# LabAccessDC.net
KiCad netlist of a schematic drawn in EAGLE
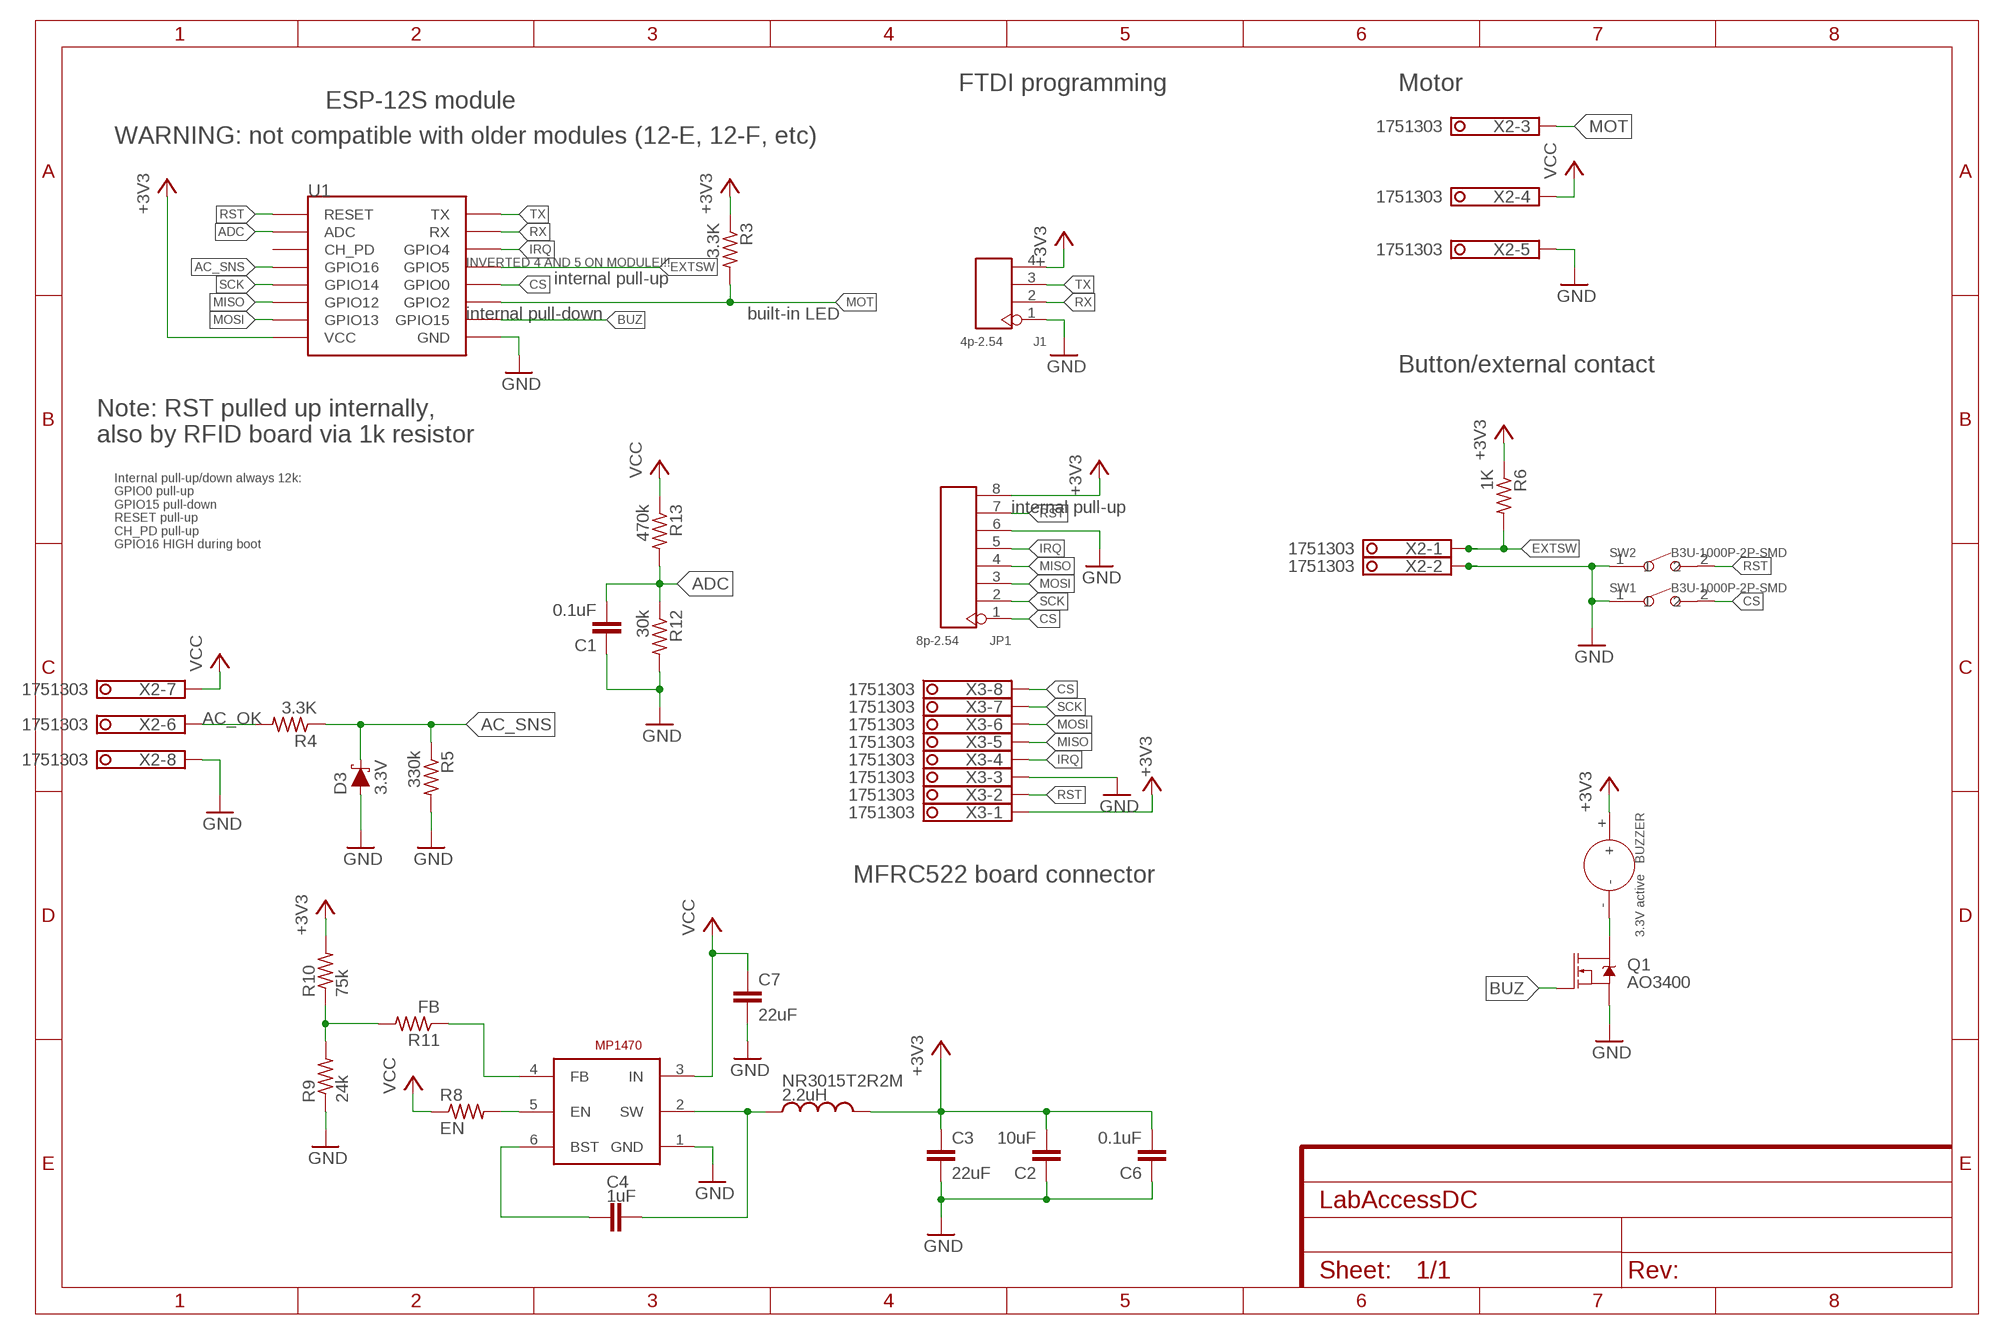
[diagram p0: schematic, sheet 1]

(export (version "E")
  (design (tool "Eeschema 10.0.6"))
  (components
    (comp (ref "BUZZER")
      (value "3.3V active")
      (footprint "eagle-import:BZ2-7.6-D12.0XH6.5MM")
      (fields (field (name "MPN") "KS-12065D03YA"))
      (libsource (lib "eagle-import") (part "DIP-BUZZER-3V(KS-12065D03YA)"))
    )
    (comp (ref "C1")
      (value "0.1uF")
      (footprint "eagle-import:C0603K")
      (libsource (lib "eagle-import") (part "C-EUC0603K"))
    )
    (comp (ref "C2")
      (value "10uF")
      (footprint "eagle-import:C0805K")
      (libsource (lib "eagle-import") (part "C-EUC0805K"))
    )
    (comp (ref "C3")
      (value "22uF")
      (footprint "eagle-import:C0805K")
      (libsource (lib "eagle-import") (part "C-EUC0805K"))
    )
    (comp (ref "C4")
      (value "1uF")
      (footprint "eagle-import:C0603K")
      (libsource (lib "eagle-import") (part "C-EUC0603K"))
    )
    (comp (ref "C6")
      (value "0.1uF")
      (footprint "eagle-import:C0603K")
      (libsource (lib "eagle-import") (part "C-EUC0603K"))
    )
    (comp (ref "C7")
      (value "22uF")
      (footprint "eagle-import:C0805K")
      (libsource (lib "eagle-import") (part "C-EUC0805K"))
    )
    (comp (ref "D3")
      (value "3.3V")
      (footprint "eagle-import:SPARKFUN-DISCRETESEMI_SOD-523")
      (fields (field (name "SPICEPREFIX") "D"))
      (libsource (lib "eagle-import") (part "SPARKFUN-DISCRETESEMI_DIODE-SCHOTTKY-RB751S40"))
    )
    (comp (ref "J1")
      (value "4p-2.54")
      (footprint "eagle-import:H4-2.54")
      (fields (field (name "MPN") "P125-1104A0BS116A1"))
      (libsource (lib "eagle-import") (part "DIP-BLACK-MALE-HEADER-VERT(4P-2.54)"))
    )
    (comp (ref "JP1")
      (value "8p-2.54")
      (footprint "eagle-import:H8-2.54")
      (fields (field (name "MPN") "P125-1108A1BS116A1"))
      (libsource (lib "eagle-import") (part "DIP-BLACK-MALE-HEADER-VERT(8P-2.54)"))
    )
    (comp (ref "MP1470")
      (value "MP1470GJ")
      (footprint "eagle-import:TSOT-23-6")
      (libsource (lib "eagle-import") (part "MP1470GJ"))
    )
    (comp (ref "NR3015T2R2M")
      (value "2.2uH")
      (footprint "eagle-import:INDUCTOR-NR3015")
      (libsource (lib "eagle-import") (part "INDUCTORB"))
    )
    (comp (ref "Q1")
      (value "AO3400")
      (footprint "eagle-import:SOT23-3")
      (libsource (lib "eagle-import") (part "MOSFET-NCH-AO3404A"))
    )
    (comp (ref "R3")
      (value "3.3K")
      (footprint "eagle-import:R0603")
      (libsource (lib "eagle-import") (part "resistor_348_R-US_R0603"))
    )
    (comp (ref "R4")
      (value "3.3K")
      (footprint "eagle-import:R0603")
      (libsource (lib "eagle-import") (part "R-US_R0603"))
    )
    (comp (ref "R5")
      (value "330k")
      (footprint "eagle-import:R0603")
      (libsource (lib "eagle-import") (part "R-US_R0603"))
    )
    (comp (ref "R6")
      (value "1K")
      (footprint "eagle-import:R0603")
      (libsource (lib "eagle-import") (part "resistor_348_R-US_R0603"))
    )
    (comp (ref "R8")
      (value "EN")
      (footprint "eagle-import:R0603")
      (libsource (lib "eagle-import") (part "R-US_R0603"))
    )
    (comp (ref "R9")
      (value "24k")
      (footprint "eagle-import:R0603")
      (libsource (lib "eagle-import") (part "R-US_R0603"))
    )
    (comp (ref "R10")
      (value "75k")
      (footprint "eagle-import:R0603")
      (libsource (lib "eagle-import") (part "R-US_R0603"))
    )
    (comp (ref "R11")
      (value "FB")
      (footprint "eagle-import:R0603")
      (libsource (lib "eagle-import") (part "R-US_R0603"))
    )
    (comp (ref "R12")
      (value "30k")
      (footprint "eagle-import:R0603")
      (libsource (lib "eagle-import") (part "R-US_R0603"))
    )
    (comp (ref "R13")
      (value "470k")
      (footprint "eagle-import:R0603")
      (libsource (lib "eagle-import") (part "R-US_R0603"))
    )
    (comp (ref "SW1")
      (value "B3U-1000P-2P-SMD")
      (footprint "eagle-import:SW2-2.6-3.0X2.5X1.2+0.4MM")
      (libsource (lib "eagle-import") (part "SMD-BUTTON(2P-3.0X2.5X1.2+0.4MM)-B3U-1000P-2P-SMD"))
    )
    (comp (ref "SW2")
      (value "B3U-1000P-2P-SMD")
      (footprint "eagle-import:SW2-2.6-3.0X2.5X1.2+0.4MM")
      (libsource (lib "eagle-import") (part "SMD-BUTTON(2P-3.0X2.5X1.2+0.4MM)-B3U-1000P-2P-SMD"))
    )
    (comp (ref "U1")
      (value "ESP12SMD")
      (footprint "eagle-import:ESP12-SMD")
      (libsource (lib "eagle-import") (part "ESP12SMD"))
    )
    (comp (ref "X2")
      (value "1751303")
      (footprint "eagle-import:1751303")
      (libsource (lib "eagle-import") (part "1751303"))
    )
    (comp (ref "X3")
      (value "1751303")
      (footprint "eagle-import:1751303")
      (libsource (lib "eagle-import") (part "1751303"))
    )
  )
  (nets
    (net (code "1") (name "+3V3") (class "Default")
      (node (ref "BUZZER") (pin "+") (pinfunction "+_+") (pintype "bidirectional"))
      (node (ref "C2") (pin "2") (pinfunction "2_2") (pintype "passive"))
      (node (ref "C3") (pin "1") (pinfunction "1_1") (pintype "passive"))
      (node (ref "C6") (pin "2") (pinfunction "2_2") (pintype "passive"))
      (node (ref "J1") (pin "4") (pinfunction "P$4_4") (pintype "bidirectional"))
      (node (ref "JP1") (pin "8") (pinfunction "8_8") (pintype "bidirectional"))
      (node (ref "NR3015T2R2M") (pin "2") (pinfunction "2_2") (pintype "passive"))
      (node (ref "R10") (pin "2") (pinfunction "2_2") (pintype "passive"))
      (node (ref "R3") (pin "1") (pinfunction "1_1") (pintype "passive"))
      (node (ref "R6") (pin "1") (pinfunction "1_1") (pintype "passive"))
      (node (ref "U1") (pin "VCC") (pinfunction "VCC_VCC") (pintype "bidirectional"))
      (node (ref "X3") (pin "1") (pinfunction "K_1") (pintype "passive"))
    )
    (net (code "2") (name "/AC_OK") (class "Default")
      (node (ref "R4") (pin "2") (pinfunction "2_2") (pintype "passive"))
      (node (ref "X2") (pin "6") (pinfunction "K_6") (pintype "passive"))
    )
    (net (code "3") (name "AC_SNS") (class "Default")
      (node (ref "D3") (pin "C") (pinfunction "C_C") (pintype "passive"))
      (node (ref "R4") (pin "1") (pinfunction "1_1") (pintype "passive"))
      (node (ref "R5") (pin "1") (pinfunction "1_1") (pintype "passive"))
      (node (ref "U1") (pin "GPIO16") (pinfunction "GPIO16_GPIO16") (pintype "bidirectional"))
    )
    (net (code "4") (name "ADC") (class "Default")
      (node (ref "C1") (pin "2") (pinfunction "2_2") (pintype "passive"))
      (node (ref "R12") (pin "1") (pinfunction "1_1") (pintype "passive"))
      (node (ref "R13") (pin "2") (pinfunction "2_2") (pintype "passive"))
      (node (ref "U1") (pin "ADC") (pinfunction "ADC_ADC") (pintype "bidirectional"))
    )
    (net (code "5") (name "BUZ") (class "Default")
      (node (ref "Q1") (pin "1") (pinfunction "G_1") (pintype "bidirectional"))
      (node (ref "U1") (pin "GPIO15") (pinfunction "GPIO15_GPIO15") (pintype "bidirectional"))
    )
    (net (code "6") (name "CS") (class "Default")
      (node (ref "JP1") (pin "1") (pinfunction "1_1") (pintype "bidirectional"))
      (node (ref "SW1") (pin "2") (pinfunction "2_2") (pintype "bidirectional"))
      (node (ref "U1") (pin "GPIO0") (pinfunction "GPIO0_GPIO0") (pintype "bidirectional"))
      (node (ref "X3") (pin "8") (pinfunction "K_8") (pintype "passive"))
    )
    (net (code "7") (name "EXTSW") (class "Default")
      (node (ref "R6") (pin "2") (pinfunction "2_2") (pintype "passive"))
      (node (ref "U1") (pin "GPIO5") (pinfunction "GPIO5_GPIO5") (pintype "bidirectional"))
      (node (ref "X2") (pin "1") (pinfunction "K_1") (pintype "passive"))
    )
    (net (code "8") (name "GND") (class "Default")
      (node (ref "C1") (pin "1") (pinfunction "1_1") (pintype "passive"))
      (node (ref "C2") (pin "1") (pinfunction "1_1") (pintype "passive"))
      (node (ref "C3") (pin "2") (pinfunction "2_2") (pintype "passive"))
      (node (ref "C6") (pin "1") (pinfunction "1_1") (pintype "passive"))
      (node (ref "C7") (pin "2") (pinfunction "2_2") (pintype "passive"))
      (node (ref "D3") (pin "A") (pinfunction "A_A") (pintype "passive"))
      (node (ref "J1") (pin "1") (pinfunction "P$1_1") (pintype "bidirectional"))
      (node (ref "JP1") (pin "6") (pinfunction "6_6") (pintype "bidirectional"))
      (node (ref "MP1470") (pin "1") (pinfunction "GND_1") (pintype "bidirectional"))
      (node (ref "Q1") (pin "2") (pinfunction "S_2") (pintype "bidirectional"))
      (node (ref "R12") (pin "2") (pinfunction "2_2") (pintype "passive"))
      (node (ref "R5") (pin "2") (pinfunction "2_2") (pintype "passive"))
      (node (ref "R9") (pin "1") (pinfunction "1_1") (pintype "passive"))
      (node (ref "SW1") (pin "1") (pinfunction "1_1") (pintype "bidirectional"))
      (node (ref "SW2") (pin "1") (pinfunction "1_1") (pintype "bidirectional"))
      (node (ref "U1") (pin "GND") (pinfunction "GND_GND") (pintype "bidirectional"))
      (node (ref "X2") (pin "2") (pinfunction "K_2") (pintype "passive"))
      (node (ref "X2") (pin "5") (pinfunction "K_5") (pintype "passive"))
      (node (ref "X2") (pin "8") (pinfunction "K_8") (pintype "passive"))
      (node (ref "X3") (pin "3") (pinfunction "K_3") (pintype "passive"))
    )
    (net (code "9") (name "IRQ") (class "Default")
      (node (ref "JP1") (pin "5") (pinfunction "5_5") (pintype "bidirectional"))
      (node (ref "U1") (pin "GPIO4") (pinfunction "GPIO4_GPIO4") (pintype "bidirectional"))
      (node (ref "X3") (pin "4") (pinfunction "K_4") (pintype "passive"))
    )
    (net (code "10") (name "MISO") (class "Default")
      (node (ref "JP1") (pin "4") (pinfunction "4_4") (pintype "bidirectional"))
      (node (ref "U1") (pin "GPIO12") (pinfunction "GPIO12_GPIO12") (pintype "bidirectional"))
      (node (ref "X3") (pin "5") (pinfunction "K_5") (pintype "passive"))
    )
    (net (code "11") (name "MOSI") (class "Default")
      (node (ref "JP1") (pin "3") (pinfunction "3_3") (pintype "bidirectional"))
      (node (ref "U1") (pin "GPIO13") (pinfunction "GPIO13_GPIO13") (pintype "bidirectional"))
      (node (ref "X3") (pin "6") (pinfunction "K_6") (pintype "passive"))
    )
    (net (code "12") (name "MOT") (class "Default")
      (node (ref "R3") (pin "2") (pinfunction "2_2") (pintype "passive"))
      (node (ref "U1") (pin "GPIO2") (pinfunction "GPIO2_GPIO2") (pintype "bidirectional"))
      (node (ref "X2") (pin "3") (pinfunction "K_3") (pintype "passive"))
    )
    (net (code "13") (name "Net-(MP1470-BST)") (class "Default")
      (node (ref "C4") (pin "1") (pinfunction "1_1") (pintype "passive"))
      (node (ref "MP1470") (pin "6") (pinfunction "BST_6") (pintype "bidirectional"))
    )
    (net (code "14") (name "Net-(MP1470-EN)") (class "Default")
      (node (ref "MP1470") (pin "5") (pinfunction "EN_5") (pintype "bidirectional"))
      (node (ref "R8") (pin "2") (pinfunction "2_2") (pintype "passive"))
    )
    (net (code "15") (name "Net-(MP1470-FB)") (class "Default")
      (node (ref "MP1470") (pin "4") (pinfunction "FB_4") (pintype "bidirectional"))
      (node (ref "R11") (pin "1") (pinfunction "1_1") (pintype "passive"))
    )
    (net (code "16") (name "Net-(MP1470-SW)") (class "Default")
      (node (ref "C4") (pin "2") (pinfunction "2_2") (pintype "passive"))
      (node (ref "MP1470") (pin "2") (pinfunction "SW_2") (pintype "bidirectional"))
      (node (ref "NR3015T2R2M") (pin "1") (pinfunction "1_1") (pintype "passive"))
    )
    (net (code "17") (name "Net-(Q1-D)") (class "Default")
      (node (ref "BUZZER") (pin "-") (pinfunction "-_-") (pintype "bidirectional"))
      (node (ref "Q1") (pin "3") (pinfunction "D_3") (pintype "bidirectional"))
    )
    (net (code "18") (name "Net-(R10-Pad1)") (class "Default")
      (node (ref "R10") (pin "1") (pinfunction "1_1") (pintype "passive"))
      (node (ref "R11") (pin "2") (pinfunction "2_2") (pintype "passive"))
      (node (ref "R9") (pin "2") (pinfunction "2_2") (pintype "passive"))
    )
    (net (code "19") (name "RST") (class "Default")
      (node (ref "JP1") (pin "7") (pinfunction "7_7") (pintype "bidirectional"))
      (node (ref "SW2") (pin "2") (pinfunction "2_2") (pintype "bidirectional"))
      (node (ref "U1") (pin "RESET") (pinfunction "RESET_RESET") (pintype "bidirectional"))
      (node (ref "X3") (pin "2") (pinfunction "K_2") (pintype "passive"))
    )
    (net (code "20") (name "RX") (class "Default")
      (node (ref "J1") (pin "2") (pinfunction "P$2_2") (pintype "bidirectional"))
      (node (ref "U1") (pin "RXD0") (pinfunction "RX_RXD0") (pintype "bidirectional"))
    )
    (net (code "21") (name "SCK") (class "Default")
      (node (ref "JP1") (pin "2") (pinfunction "2_2") (pintype "bidirectional"))
      (node (ref "U1") (pin "GPIO14") (pinfunction "GPIO14_GPIO14") (pintype "bidirectional"))
      (node (ref "X3") (pin "7") (pinfunction "K_7") (pintype "passive"))
    )
    (net (code "22") (name "TX") (class "Default")
      (node (ref "J1") (pin "3") (pinfunction "P$3_3") (pintype "bidirectional"))
      (node (ref "U1") (pin "TXD0") (pinfunction "TX_TXD0") (pintype "bidirectional"))
    )
    (net (code "23") (name "VCC") (class "Default")
      (node (ref "C7") (pin "1") (pinfunction "1_1") (pintype "passive"))
      (node (ref "MP1470") (pin "3") (pinfunction "IN_3") (pintype "bidirectional"))
      (node (ref "R13") (pin "1") (pinfunction "1_1") (pintype "passive"))
      (node (ref "R8") (pin "1") (pinfunction "1_1") (pintype "passive"))
      (node (ref "X2") (pin "4") (pinfunction "K_4") (pintype "passive"))
      (node (ref "X2") (pin "7") (pinfunction "K_7") (pintype "passive"))
    )
    (net (code "24") (name "unconnected-(U1-PadCH_PD)") (class "Default")
      (node (ref "U1") (pin "CH_PD") (pinfunction "CH_PD_CH_PD") (pintype "bidirectional"))
    )
  )
)
